# ic735-bandswitch.net
KiCad netlist of a schematic drawn in EAGLE
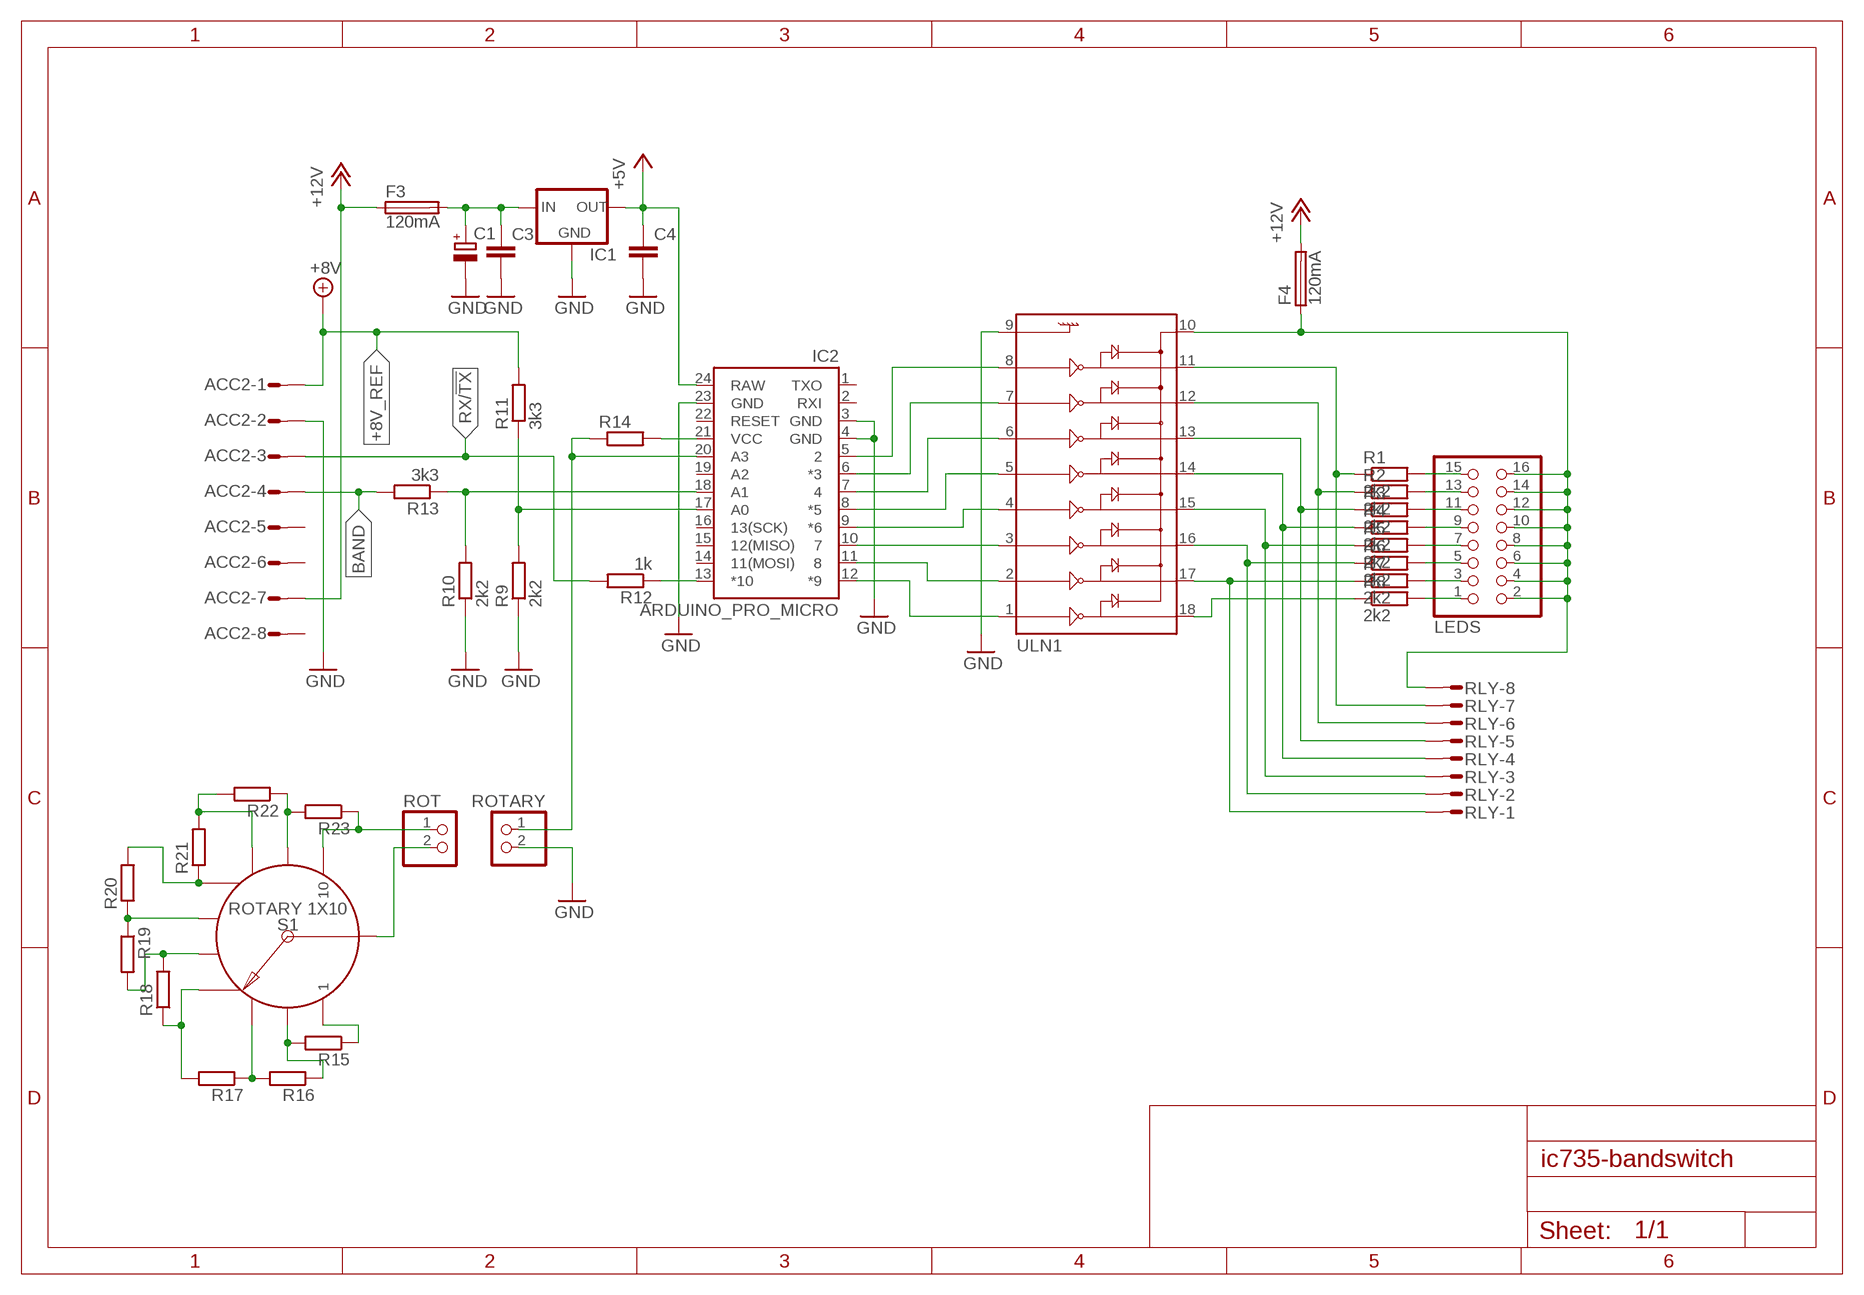
[diagram p0: schematic, sheet 1]

(export (version "E")
  (design (tool "Eeschema 10.0.6"))
  (components
    (comp (ref "ACC2")
      (value "S08P")
      (footprint "eagle-import:S08P")
      (libsource (lib "eagle-import") (part "S08P"))
    )
    (comp (ref "C1")
      (value "CPOL-EUE2,5-6E")
      (footprint "eagle-import:E2,5-6E")
      (libsource (lib "eagle-import") (part "CPOL-EUE2,5-6E"))
    )
    (comp (ref "C3")
      (value "C-EU025-024X044")
      (footprint "eagle-import:C025-024X044")
      (libsource (lib "eagle-import") (part "C-EU025-024X044"))
    )
    (comp (ref "C4")
      (value "C-EU025-024X044")
      (footprint "eagle-import:C025-024X044")
      (libsource (lib "eagle-import") (part "C-EU025-024X044"))
    )
    (comp (ref "F3")
      (value "120mA")
      (footprint "eagle-import:TE5")
      (libsource (lib "eagle-import") (part "TE5"))
    )
    (comp (ref "F4")
      (value "120mA")
      (footprint "eagle-import:TE5")
      (libsource (lib "eagle-import") (part "TE5"))
    )
    (comp (ref "IC1")
      (value "78XXS")
      (footprint "eagle-import:78XXS")
      (libsource (lib "eagle-import") (part "78XXS"))
    )
    (comp (ref "IC2")
      (value "ARDUINO_PRO_MICRO")
      (footprint "eagle-import:ARDUINO_PRO_MICRO")
      (libsource (lib "eagle-import") (part "ARDUINO_PRO_MICRO"))
    )
    (comp (ref "LEDS")
      (value "PINHD-2X8")
      (footprint "eagle-import:2X08")
      (libsource (lib "eagle-import") (part "PINHD-2X8"))
    )
    (comp (ref "R1")
      (value "2k2")
      (footprint "eagle-import:R0603")
      (libsource (lib "eagle-import") (part "R-EU_R0603"))
    )
    (comp (ref "R2")
      (value "2k2")
      (footprint "eagle-import:R0603")
      (libsource (lib "eagle-import") (part "R-EU_R0603"))
    )
    (comp (ref "R3")
      (value "2k2")
      (footprint "eagle-import:R0603")
      (libsource (lib "eagle-import") (part "R-EU_R0603"))
    )
    (comp (ref "R4")
      (value "2k2")
      (footprint "eagle-import:R0603")
      (libsource (lib "eagle-import") (part "R-EU_R0603"))
    )
    (comp (ref "R5")
      (value "2k2")
      (footprint "eagle-import:R0603")
      (libsource (lib "eagle-import") (part "R-EU_R0603"))
    )
    (comp (ref "R6")
      (value "2k2")
      (footprint "eagle-import:R0603")
      (libsource (lib "eagle-import") (part "R-EU_R0603"))
    )
    (comp (ref "R7")
      (value "2k2")
      (footprint "eagle-import:R0603")
      (libsource (lib "eagle-import") (part "R-EU_R0603"))
    )
    (comp (ref "R8")
      (value "2k2")
      (footprint "eagle-import:R0603")
      (libsource (lib "eagle-import") (part "R-EU_R0603"))
    )
    (comp (ref "R9")
      (value "2k2")
      (footprint "eagle-import:R0603")
      (libsource (lib "eagle-import") (part "R-EU_R0603"))
    )
    (comp (ref "R10")
      (value "2k2")
      (footprint "eagle-import:R0603")
      (libsource (lib "eagle-import") (part "R-EU_R0603"))
    )
    (comp (ref "R11")
      (value "3k3")
      (footprint "eagle-import:R0603")
      (libsource (lib "eagle-import") (part "R-EU_R0603"))
    )
    (comp (ref "R12")
      (value "1k")
      (footprint "eagle-import:R0603")
      (libsource (lib "eagle-import") (part "R-EU_R0603"))
    )
    (comp (ref "R13")
      (value "3k3")
      (footprint "eagle-import:R0603")
      (libsource (lib "eagle-import") (part "R-EU_R0603"))
    )
    (comp (ref "R14")
      (value "R-EU_R0603")
      (footprint "eagle-import:R0603")
      (libsource (lib "eagle-import") (part "R-EU_R0603"))
    )
    (comp (ref "R15")
      (value "R-EU_R0603")
      (footprint "eagle-import:R0603")
      (libsource (lib "eagle-import") (part "R-EU_R0603"))
    )
    (comp (ref "R16")
      (value "R-EU_R0603")
      (footprint "eagle-import:R0603")
      (libsource (lib "eagle-import") (part "R-EU_R0603"))
    )
    (comp (ref "R17")
      (value "R-EU_R0603")
      (footprint "eagle-import:R0603")
      (libsource (lib "eagle-import") (part "R-EU_R0603"))
    )
    (comp (ref "R18")
      (value "R-EU_R0603")
      (footprint "eagle-import:R0603")
      (libsource (lib "eagle-import") (part "R-EU_R0603"))
    )
    (comp (ref "R19")
      (value "R-EU_R0603")
      (footprint "eagle-import:R0603")
      (libsource (lib "eagle-import") (part "R-EU_R0603"))
    )
    (comp (ref "R20")
      (value "R-EU_R0603")
      (footprint "eagle-import:R0603")
      (libsource (lib "eagle-import") (part "R-EU_R0603"))
    )
    (comp (ref "R21")
      (value "R-EU_R0603")
      (footprint "eagle-import:R0603")
      (libsource (lib "eagle-import") (part "R-EU_R0603"))
    )
    (comp (ref "R22")
      (value "R-EU_R0603")
      (footprint "eagle-import:R0603")
      (libsource (lib "eagle-import") (part "R-EU_R0603"))
    )
    (comp (ref "R23")
      (value "R-EU_R0603")
      (footprint "eagle-import:R0603")
      (libsource (lib "eagle-import") (part "R-EU_R0603"))
    )
    (comp (ref "RLY")
      (value "S08P")
      (footprint "eagle-import:S08P")
      (libsource (lib "eagle-import") (part "S08P"))
    )
    (comp (ref "ROT")
      (value "PINHD-1X2")
      (footprint "eagle-import:1X02")
      (libsource (lib "eagle-import") (part "PINHD-1X2"))
    )
    (comp (ref "ROTARY")
      (value "PINHD-1X2")
      (footprint "eagle-import:1X02")
      (libsource (lib "eagle-import") (part "PINHD-1X2"))
    )
    (comp (ref "S1")
      (value "ROTARY 1X10")
      (footprint "eagle-import:ROTARY_SWITCH_1X10")
      (libsource (lib "eagle-import") (part "SWITCH_ROTARY_1X10-PTH"))
    )
    (comp (ref "ULN1")
      (value "ULN2803DIP")
      (footprint "eagle-import:DIL18")
      (libsource (lib "eagle-import") (part "ULN2803DIP"))
    )
  )
  (nets
    (net (code "1") (name "+5V") (class "Default")
      (node (ref "C4") (pin "1") (pinfunction "1_1") (pintype "passive"))
      (node (ref "IC1") (pin "OUT") (pinfunction "OUT_OUT") (pintype "passive"))
      (node (ref "IC2") (pin "24") (pinfunction "RAW_24") (pintype "bidirectional"))
    )
    (net (code "2") (name "+8V_REF") (class "Default")
      (node (ref "ACC2") (pin "1") (pinfunction "S_1") (pintype "passive"))
      (node (ref "R11") (pin "2") (pinfunction "2_2") (pintype "passive"))
    )
    (net (code "3") (name "+12V") (class "Default")
      (node (ref "ACC2") (pin "7") (pinfunction "S_7") (pintype "passive"))
      (node (ref "F3") (pin "1") (pinfunction "1_1") (pintype "passive"))
      (node (ref "F4") (pin "2") (pinfunction "2_2") (pintype "passive"))
    )
    (net (code "4") (name "/RX{slash}~{TX}") (class "Default")
      (node (ref "ACC2") (pin "3") (pinfunction "S_3") (pintype "passive"))
      (node (ref "R12") (pin "2") (pinfunction "2_2") (pintype "passive"))
    )
    (net (code "5") (name "BAND") (class "Default")
      (node (ref "ACC2") (pin "4") (pinfunction "S_4") (pintype "passive"))
      (node (ref "R13") (pin "2") (pinfunction "2_2") (pintype "passive"))
    )
    (net (code "6") (name "GND") (class "Default")
      (node (ref "ACC2") (pin "2") (pinfunction "S_2") (pintype "passive"))
      (node (ref "C1") (pin "-") (pinfunction "-_-") (pintype "passive"))
      (node (ref "C3") (pin "2") (pinfunction "2_2") (pintype "passive"))
      (node (ref "C4") (pin "2") (pinfunction "2_2") (pintype "passive"))
      (node (ref "IC1") (pin "GND") (pinfunction "GND_GND") (pintype "input"))
      (node (ref "IC2") (pin "23") (pinfunction "GND_23") (pintype "bidirectional"))
      (node (ref "IC2") (pin "3") (pinfunction "GND_3") (pintype "bidirectional"))
      (node (ref "IC2") (pin "4") (pinfunction "GND_4") (pintype "bidirectional"))
      (node (ref "R10") (pin "1") (pinfunction "1_1") (pintype "passive"))
      (node (ref "R9") (pin "1") (pinfunction "1_1") (pintype "passive"))
      (node (ref "ROTARY") (pin "2") (pinfunction "2_2") (pintype "passive"))
      (node (ref "ULN1") (pin "9") (pinfunction "9_9") (pintype "bidirectional"))
    )
    (net (code "7") (name "Net-(C1-Pad+)") (class "Default")
      (node (ref "C1") (pin "+") (pinfunction "+_+") (pintype "passive"))
      (node (ref "C3") (pin "1") (pinfunction "1_1") (pintype "passive"))
      (node (ref "F3") (pin "2") (pinfunction "2_2") (pintype "passive"))
      (node (ref "IC1") (pin "IN") (pinfunction "IN_IN") (pintype "input"))
    )
    (net (code "8") (name "Net-(IC2-*3)") (class "Default")
      (node (ref "IC2") (pin "6") (pinfunction "*3_6") (pintype "bidirectional"))
      (node (ref "ULN1") (pin "7") (pinfunction "7_7") (pintype "bidirectional"))
    )
    (net (code "9") (name "Net-(IC2-*5)") (class "Default")
      (node (ref "IC2") (pin "8") (pinfunction "*5_8") (pintype "bidirectional"))
      (node (ref "ULN1") (pin "5") (pinfunction "5_5") (pintype "bidirectional"))
    )
    (net (code "10") (name "Net-(IC2-*6)") (class "Default")
      (node (ref "IC2") (pin "9") (pinfunction "*6_9") (pintype "bidirectional"))
      (node (ref "ULN1") (pin "4") (pinfunction "4_4") (pintype "bidirectional"))
    )
    (net (code "11") (name "Net-(IC2-*9)") (class "Default")
      (node (ref "IC2") (pin "12") (pinfunction "*9_12") (pintype "bidirectional"))
      (node (ref "ULN1") (pin "1") (pinfunction "1_1") (pintype "bidirectional"))
    )
    (net (code "12") (name "Net-(IC2-*10)") (class "Default")
      (node (ref "IC2") (pin "13") (pinfunction "*10_13") (pintype "bidirectional"))
      (node (ref "R12") (pin "1") (pinfunction "1_1") (pintype "passive"))
    )
    (net (code "13") (name "Net-(IC2-2)") (class "Default")
      (node (ref "IC2") (pin "5") (pinfunction "2_5") (pintype "bidirectional"))
      (node (ref "ULN1") (pin "8") (pinfunction "8_8") (pintype "bidirectional"))
    )
    (net (code "14") (name "Net-(IC2-4)") (class "Default")
      (node (ref "IC2") (pin "7") (pinfunction "4_7") (pintype "bidirectional"))
      (node (ref "ULN1") (pin "6") (pinfunction "6_6") (pintype "bidirectional"))
    )
    (net (code "15") (name "Net-(IC2-7)") (class "Default")
      (node (ref "IC2") (pin "10") (pinfunction "7_10") (pintype "bidirectional"))
      (node (ref "ULN1") (pin "3") (pinfunction "3_3") (pintype "bidirectional"))
    )
    (net (code "16") (name "Net-(IC2-8)") (class "Default")
      (node (ref "IC2") (pin "11") (pinfunction "8_11") (pintype "bidirectional"))
      (node (ref "ULN1") (pin "2") (pinfunction "2_2") (pintype "bidirectional"))
    )
    (net (code "17") (name "Net-(IC2-A0)") (class "Default")
      (node (ref "IC2") (pin "17") (pinfunction "A0_17") (pintype "bidirectional"))
      (node (ref "R11") (pin "1") (pinfunction "1_1") (pintype "passive"))
      (node (ref "R9") (pin "2") (pinfunction "2_2") (pintype "passive"))
    )
    (net (code "18") (name "Net-(IC2-A1)") (class "Default")
      (node (ref "IC2") (pin "18") (pinfunction "A1_18") (pintype "bidirectional"))
      (node (ref "R10") (pin "2") (pinfunction "2_2") (pintype "passive"))
      (node (ref "R13") (pin "1") (pinfunction "1_1") (pintype "passive"))
    )
    (net (code "19") (name "Net-(IC2-A3)") (class "Default")
      (node (ref "IC2") (pin "20") (pinfunction "A3_20") (pintype "bidirectional"))
      (node (ref "R14") (pin "1") (pinfunction "1_1") (pintype "passive"))
      (node (ref "ROTARY") (pin "1") (pinfunction "1_1") (pintype "passive"))
    )
    (net (code "20") (name "Net-(IC2-VCC)") (class "Default")
      (node (ref "IC2") (pin "21") (pinfunction "VCC_21") (pintype "bidirectional"))
      (node (ref "R14") (pin "2") (pinfunction "2_2") (pintype "passive"))
    )
    (net (code "21") (name "Net-(LEDS-Pad1)") (class "Default")
      (node (ref "LEDS") (pin "1") (pinfunction "1_1") (pintype "passive"))
      (node (ref "R8") (pin "2") (pinfunction "2_2") (pintype "passive"))
    )
    (net (code "22") (name "Net-(LEDS-Pad3)") (class "Default")
      (node (ref "LEDS") (pin "3") (pinfunction "3_3") (pintype "passive"))
      (node (ref "R7") (pin "2") (pinfunction "2_2") (pintype "passive"))
    )
    (net (code "23") (name "Net-(LEDS-Pad5)") (class "Default")
      (node (ref "LEDS") (pin "5") (pinfunction "5_5") (pintype "passive"))
      (node (ref "R6") (pin "2") (pinfunction "2_2") (pintype "passive"))
    )
    (net (code "24") (name "Net-(LEDS-Pad7)") (class "Default")
      (node (ref "LEDS") (pin "7") (pinfunction "7_7") (pintype "passive"))
      (node (ref "R5") (pin "2") (pinfunction "2_2") (pintype "passive"))
    )
    (net (code "25") (name "Net-(LEDS-Pad9)") (class "Default")
      (node (ref "LEDS") (pin "9") (pinfunction "9_9") (pintype "passive"))
      (node (ref "R4") (pin "2") (pinfunction "2_2") (pintype "passive"))
    )
    (net (code "26") (name "Net-(LEDS-Pad11)") (class "Default")
      (node (ref "LEDS") (pin "11") (pinfunction "11_11") (pintype "passive"))
      (node (ref "R3") (pin "2") (pinfunction "2_2") (pintype "passive"))
    )
    (net (code "27") (name "Net-(LEDS-Pad13)") (class "Default")
      (node (ref "LEDS") (pin "13") (pinfunction "13_13") (pintype "passive"))
      (node (ref "R2") (pin "2") (pinfunction "2_2") (pintype "passive"))
    )
    (net (code "28") (name "Net-(LEDS-Pad15)") (class "Default")
      (node (ref "LEDS") (pin "15") (pinfunction "15_15") (pintype "passive"))
      (node (ref "R1") (pin "2") (pinfunction "2_2") (pintype "passive"))
    )
    (net (code "29") (name "Net-(R8-Pad1)") (class "Default")
      (node (ref "R8") (pin "1") (pinfunction "1_1") (pintype "passive"))
      (node (ref "ULN1") (pin "18") (pinfunction "18_18") (pintype "bidirectional"))
    )
    (net (code "30") (name "Net-(R15-Pad1)") (class "Default")
      (node (ref "R15") (pin "1") (pinfunction "1_1") (pintype "passive"))
      (node (ref "S1") (pin "1") (pinfunction "1_1") (pintype "bidirectional"))
    )
    (net (code "31") (name "Net-(R15-Pad2)") (class "Default")
      (node (ref "R15") (pin "2") (pinfunction "2_2") (pintype "passive"))
      (node (ref "R16") (pin "1") (pinfunction "1_1") (pintype "passive"))
      (node (ref "S1") (pin "2") (pinfunction "2_2") (pintype "bidirectional"))
    )
    (net (code "32") (name "Net-(R16-Pad2)") (class "Default")
      (node (ref "R16") (pin "2") (pinfunction "2_2") (pintype "passive"))
      (node (ref "R17") (pin "1") (pinfunction "1_1") (pintype "passive"))
      (node (ref "S1") (pin "3") (pinfunction "3_3") (pintype "bidirectional"))
    )
    (net (code "33") (name "Net-(R17-Pad2)") (class "Default")
      (node (ref "R17") (pin "2") (pinfunction "2_2") (pintype "passive"))
      (node (ref "R18") (pin "1") (pinfunction "1_1") (pintype "passive"))
      (node (ref "S1") (pin "4") (pinfunction "4_4") (pintype "bidirectional"))
    )
    (net (code "34") (name "Net-(R18-Pad2)") (class "Default")
      (node (ref "R18") (pin "2") (pinfunction "2_2") (pintype "passive"))
      (node (ref "R19") (pin "2") (pinfunction "2_2") (pintype "passive"))
      (node (ref "S1") (pin "5") (pinfunction "5_5") (pintype "bidirectional"))
    )
    (net (code "35") (name "Net-(R19-Pad1)") (class "Default")
      (node (ref "R19") (pin "1") (pinfunction "1_1") (pintype "passive"))
      (node (ref "R20") (pin "1") (pinfunction "1_1") (pintype "passive"))
      (node (ref "S1") (pin "6") (pinfunction "6_6") (pintype "bidirectional"))
    )
    (net (code "36") (name "Net-(R20-Pad2)") (class "Default")
      (node (ref "R20") (pin "2") (pinfunction "2_2") (pintype "passive"))
      (node (ref "R21") (pin "1") (pinfunction "1_1") (pintype "passive"))
      (node (ref "S1") (pin "7") (pinfunction "7_7") (pintype "bidirectional"))
    )
    (net (code "37") (name "Net-(R21-Pad2)") (class "Default")
      (node (ref "R21") (pin "2") (pinfunction "2_2") (pintype "passive"))
      (node (ref "R22") (pin "2") (pinfunction "2_2") (pintype "passive"))
      (node (ref "S1") (pin "8") (pinfunction "8_8") (pintype "bidirectional"))
    )
    (net (code "38") (name "Net-(R22-Pad1)") (class "Default")
      (node (ref "R22") (pin "1") (pinfunction "1_1") (pintype "passive"))
      (node (ref "R23") (pin "2") (pinfunction "2_2") (pintype "passive"))
      (node (ref "S1") (pin "9") (pinfunction "9_9") (pintype "bidirectional"))
    )
    (net (code "39") (name "Net-(R23-Pad1)") (class "Default")
      (node (ref "R23") (pin "1") (pinfunction "1_1") (pintype "passive"))
      (node (ref "ROT") (pin "1") (pinfunction "1_1") (pintype "passive"))
      (node (ref "S1") (pin "10") (pinfunction "10_10") (pintype "bidirectional"))
    )
    (net (code "40") (name "Net-(RLYA-S)") (class "Default")
      (node (ref "R7") (pin "1") (pinfunction "1_1") (pintype "passive"))
      (node (ref "RLY") (pin "1") (pinfunction "S_1") (pintype "passive"))
      (node (ref "ULN1") (pin "17") (pinfunction "17_17") (pintype "bidirectional"))
    )
    (net (code "41") (name "Net-(RLYB-S)") (class "Default")
      (node (ref "R6") (pin "1") (pinfunction "1_1") (pintype "passive"))
      (node (ref "RLY") (pin "2") (pinfunction "S_2") (pintype "passive"))
      (node (ref "ULN1") (pin "16") (pinfunction "16_16") (pintype "bidirectional"))
    )
    (net (code "42") (name "Net-(RLYC-S)") (class "Default")
      (node (ref "R5") (pin "1") (pinfunction "1_1") (pintype "passive"))
      (node (ref "RLY") (pin "3") (pinfunction "S_3") (pintype "passive"))
      (node (ref "ULN1") (pin "15") (pinfunction "15_15") (pintype "bidirectional"))
    )
    (net (code "43") (name "Net-(RLYD-S)") (class "Default")
      (node (ref "R4") (pin "1") (pinfunction "1_1") (pintype "passive"))
      (node (ref "RLY") (pin "4") (pinfunction "S_4") (pintype "passive"))
      (node (ref "ULN1") (pin "14") (pinfunction "14_14") (pintype "bidirectional"))
    )
    (net (code "44") (name "Net-(RLYE-S)") (class "Default")
      (node (ref "R3") (pin "1") (pinfunction "1_1") (pintype "passive"))
      (node (ref "RLY") (pin "5") (pinfunction "S_5") (pintype "passive"))
      (node (ref "ULN1") (pin "13") (pinfunction "13_13") (pintype "bidirectional"))
    )
    (net (code "45") (name "Net-(RLYF-S)") (class "Default")
      (node (ref "R2") (pin "1") (pinfunction "1_1") (pintype "passive"))
      (node (ref "RLY") (pin "6") (pinfunction "S_6") (pintype "passive"))
      (node (ref "ULN1") (pin "12") (pinfunction "12_12") (pintype "bidirectional"))
    )
    (net (code "46") (name "Net-(RLYG-S)") (class "Default")
      (node (ref "R1") (pin "1") (pinfunction "1_1") (pintype "passive"))
      (node (ref "RLY") (pin "7") (pinfunction "S_7") (pintype "passive"))
      (node (ref "ULN1") (pin "11") (pinfunction "11_11") (pintype "bidirectional"))
    )
    (net (code "47") (name "Net-(RLYH-S)") (class "Default")
      (node (ref "F4") (pin "1") (pinfunction "1_1") (pintype "passive"))
      (node (ref "LEDS") (pin "10") (pinfunction "10_10") (pintype "passive"))
      (node (ref "LEDS") (pin "12") (pinfunction "12_12") (pintype "passive"))
      (node (ref "LEDS") (pin "14") (pinfunction "14_14") (pintype "passive"))
      (node (ref "LEDS") (pin "16") (pinfunction "16_16") (pintype "passive"))
      (node (ref "LEDS") (pin "2") (pinfunction "2_2") (pintype "passive"))
      (node (ref "LEDS") (pin "4") (pinfunction "4_4") (pintype "passive"))
      (node (ref "LEDS") (pin "6") (pinfunction "6_6") (pintype "passive"))
      (node (ref "LEDS") (pin "8") (pinfunction "8_8") (pintype "passive"))
      (node (ref "RLY") (pin "8") (pinfunction "S_8") (pintype "passive"))
      (node (ref "ULN1") (pin "10") (pinfunction "10_10") (pintype "bidirectional"))
    )
    (net (code "48") (name "Net-(ROT-Pad2)") (class "Default")
      (node (ref "ROT") (pin "2") (pinfunction "2_2") (pintype "passive"))
      (node (ref "S1") (pin "COMMON") (pinfunction "COMMON_COMMON") (pintype "bidirectional"))
    )
    (net (code "49") (name "unconnected-(ACC2E-S-Pad5)") (class "Default")
      (node (ref "ACC2") (pin "5") (pinfunction "S_5") (pintype "passive"))
    )
    (net (code "50") (name "unconnected-(ACC2F-S-Pad6)") (class "Default")
      (node (ref "ACC2") (pin "6") (pinfunction "S_6") (pintype "passive"))
    )
    (net (code "51") (name "unconnected-(ACC2H-S-Pad8)") (class "Default")
      (node (ref "ACC2") (pin "8") (pinfunction "S_8") (pintype "passive"))
    )
    (net (code "52") (name "unconnected-(IC2-11(MOSI)-Pad14)") (class "Default")
      (node (ref "IC2") (pin "14") (pinfunction "11(MOSI)_14") (pintype "bidirectional"))
    )
    (net (code "53") (name "unconnected-(IC2-12(MISO)-Pad15)") (class "Default")
      (node (ref "IC2") (pin "15") (pinfunction "12(MISO)_15") (pintype "bidirectional"))
    )
    (net (code "54") (name "unconnected-(IC2-13(SCK)-Pad16)") (class "Default")
      (node (ref "IC2") (pin "16") (pinfunction "13(SCK)_16") (pintype "bidirectional"))
    )
    (net (code "55") (name "unconnected-(IC2-A2-Pad19)") (class "Default")
      (node (ref "IC2") (pin "19") (pinfunction "A2_19") (pintype "bidirectional"))
    )
    (net (code "56") (name "unconnected-(IC2-RESET-Pad22)") (class "Default")
      (node (ref "IC2") (pin "22") (pinfunction "RESET_22") (pintype "bidirectional"))
    )
    (net (code "57") (name "unconnected-(IC2-RXI-Pad2)") (class "Default")
      (node (ref "IC2") (pin "2") (pinfunction "RXI_2") (pintype "bidirectional"))
    )
    (net (code "58") (name "unconnected-(IC2-TXO-Pad1)") (class "Default")
      (node (ref "IC2") (pin "1") (pinfunction "TXO_1") (pintype "bidirectional"))
    )
  )
)
